# schematic.net
KiCad netlist of a schematic drawn in EAGLE
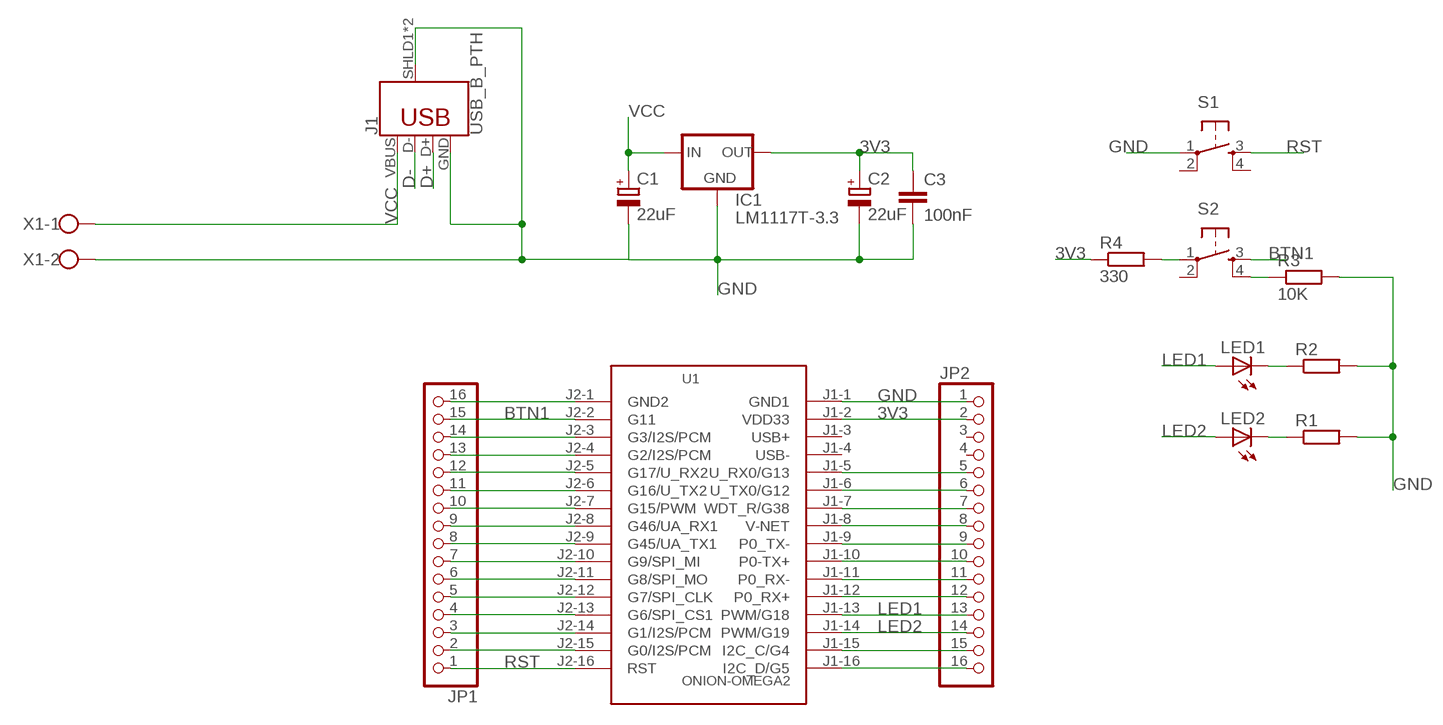
[diagram p0: schematic, sheet 1]

(export (version "E")
  (design (tool "Eeschema 10.0.6"))
  (components
    (comp (ref "C1")
      (value "22uF")
      (footprint "eagle-import:E2,5-5")
      (libsource (lib "eagle-import") (part "CPOL-EUE2.5-5"))
    )
    (comp (ref "C2")
      (value "22uF")
      (footprint "eagle-import:E2,5-5")
      (libsource (lib "eagle-import") (part "CPOL-EUE2.5-5"))
    )
    (comp (ref "C3")
      (value "100nF")
      (footprint "eagle-import:C050-025X075")
      (libsource (lib "eagle-import") (part "C-EU050-025X075"))
    )
    (comp (ref "IC1")
      (value "LM1117T-3.3")
      (footprint "eagle-import:TO220")
      (libsource (lib "eagle-import") (part "LM1117T-3.3"))
    )
    (comp (ref "J1")
      (value "USB_B_PTH")
      (footprint "eagle-import:USB-B-PTH")
      (libsource (lib "eagle-import") (part "USB_B_PTH"))
    )
    (comp (ref "JP1")
      (value "PINHD-1X16")
      (footprint "eagle-import:1X16")
      (libsource (lib "eagle-import") (part "PINHD-1X16"))
    )
    (comp (ref "JP2")
      (value "PINHD-1X16")
      (footprint "eagle-import:1X16")
      (libsource (lib "eagle-import") (part "PINHD-1X16"))
    )
    (comp (ref "LED1")
      (value "LED5MM")
      (footprint "eagle-import:LED5MM")
      (libsource (lib "eagle-import") (part "LED5MM"))
    )
    (comp (ref "LED2")
      (value "LED5MM")
      (footprint "eagle-import:LED5MM")
      (libsource (lib "eagle-import") (part "LED5MM"))
    )
    (comp (ref "R1")
      (value "R-EU_0204/7")
      (footprint "eagle-import:0204_7")
      (libsource (lib "eagle-import") (part "R-EU_0204/7"))
    )
    (comp (ref "R2")
      (value "R-EU_0204/7")
      (footprint "eagle-import:0204_7")
      (libsource (lib "eagle-import") (part "R-EU_0204/7"))
    )
    (comp (ref "R3")
      (value "10K")
      (footprint "eagle-import:0204_7")
      (libsource (lib "eagle-import") (part "R-EU_0204/7"))
    )
    (comp (ref "R4")
      (value "330")
      (footprint "eagle-import:0204_7")
      (libsource (lib "eagle-import") (part "R-EU_0204/7"))
    )
    (comp (ref "S1")
      (value "TAC_SWITCHPTH")
      (footprint "eagle-import:TACTILE-PTH")
      (libsource (lib "eagle-import") (part "TAC_SWITCHPTH"))
    )
    (comp (ref "S2")
      (value "TAC_SWITCHPTH")
      (footprint "eagle-import:TACTILE-PTH")
      (libsource (lib "eagle-import") (part "TAC_SWITCHPTH"))
    )
    (comp (ref "U1")
      (value "ONION-OMEGA2")
      (footprint "eagle-import:ONION-2MM-2X16")
      (libsource (lib "eagle-import") (part "ONION-OMEGA2"))
    )
    (comp (ref "X1")
      (value "W237-102")
      (footprint "eagle-import:W237-102")
      (fields (field (name "MPN") "237-102"))
      (libsource (lib "eagle-import") (part "W237-102"))
    )
  )
  (nets
    (net (code "1") (name "/3V3") (class "Default")
      (node (ref "C2") (pin "+") (pinfunction "+_+") (pintype "passive"))
      (node (ref "C3") (pin "1") (pinfunction "1_1") (pintype "passive"))
      (node (ref "IC1") (pin "2") (pinfunction "OUT_2") (pintype "passive"))
      (node (ref "JP2") (pin "2") (pinfunction "2_2") (pintype "passive"))
      (node (ref "R4") (pin "1") (pinfunction "1_1") (pintype "passive"))
      (node (ref "U1") (pin "J1-2") (pinfunction "VDD33_J1-2") (pintype "bidirectional"))
    )
    (net (code "2") (name "/BTN1") (class "Default")
      (node (ref "JP1") (pin "15") (pinfunction "15_15") (pintype "passive"))
      (node (ref "S2") (pin "3") (pinfunction "3_3") (pintype "passive"))
      (node (ref "U1") (pin "J2-2") (pinfunction "G11_J2-2") (pintype "bidirectional"))
    )
    (net (code "3") (name "/D+") (class "Default")
      (node (ref "J1") (pin "D+") (pinfunction "D+_D+") (pintype "bidirectional"))
    )
    (net (code "4") (name "/D-") (class "Default")
      (node (ref "J1") (pin "D-") (pinfunction "D-_D-") (pintype "bidirectional"))
    )
    (net (code "5") (name "/GND") (class "Default")
      (node (ref "C1") (pin "-") (pinfunction "-_-") (pintype "passive"))
      (node (ref "C2") (pin "-") (pinfunction "-_-") (pintype "passive"))
      (node (ref "C3") (pin "2") (pinfunction "2_2") (pintype "passive"))
      (node (ref "IC1") (pin "1") (pinfunction "GND_1") (pintype "input"))
      (node (ref "J1") (pin "GND") (pinfunction "GND_GND") (pintype "power_in"))
      (node (ref "J1") (pin "SHLD1") (pinfunction "SHIELD_SHLD1") (pintype "bidirectional"))
      (node (ref "J1") (pin "SHLD2") (pinfunction "SHIELD_SHLD2") (pintype "bidirectional"))
      (node (ref "JP2") (pin "1") (pinfunction "1_1") (pintype "passive"))
      (node (ref "R1") (pin "2") (pinfunction "2_2") (pintype "passive"))
      (node (ref "R2") (pin "2") (pinfunction "2_2") (pintype "passive"))
      (node (ref "R3") (pin "2") (pinfunction "2_2") (pintype "passive"))
      (node (ref "S1") (pin "1") (pinfunction "1_1") (pintype "passive"))
      (node (ref "U1") (pin "J1-1") (pinfunction "GND1_J1-1") (pintype "bidirectional"))
      (node (ref "X1") (pin "2") (pinfunction "KL_2") (pintype "passive"))
    )
    (net (code "6") (name "/LED1") (class "Default")
      (node (ref "JP2") (pin "13") (pinfunction "13_13") (pintype "passive"))
      (node (ref "LED1") (pin "A") (pinfunction "A_A") (pintype "passive"))
      (node (ref "U1") (pin "J1-13") (pinfunction "PWM/G18_J1-13") (pintype "bidirectional"))
    )
    (net (code "7") (name "/LED2") (class "Default")
      (node (ref "JP2") (pin "14") (pinfunction "14_14") (pintype "passive"))
      (node (ref "LED2") (pin "A") (pinfunction "A_A") (pintype "passive"))
      (node (ref "U1") (pin "J1-14") (pinfunction "PWM/G19_J1-14") (pintype "bidirectional"))
    )
    (net (code "8") (name "/RST") (class "Default")
      (node (ref "JP1") (pin "1") (pinfunction "1_1") (pintype "passive"))
      (node (ref "S1") (pin "3") (pinfunction "3_3") (pintype "passive"))
      (node (ref "U1") (pin "J2-16") (pinfunction "RST_J2-16") (pintype "bidirectional"))
    )
    (net (code "9") (name "/VCC") (class "Default")
      (node (ref "C1") (pin "+") (pinfunction "+_+") (pintype "passive"))
      (node (ref "IC1") (pin "3") (pinfunction "IN_3") (pintype "input"))
      (node (ref "J1") (pin "VBUS") (pinfunction "VBUS_VBUS") (pintype "power_in"))
      (node (ref "X1") (pin "1") (pinfunction "KL_1") (pintype "passive"))
    )
    (net (code "10") (name "Net-(LED1-C)") (class "Default")
      (node (ref "LED1") (pin "K") (pinfunction "C_K") (pintype "passive"))
      (node (ref "R2") (pin "1") (pinfunction "1_1") (pintype "passive"))
    )
    (net (code "11") (name "Net-(LED2-C)") (class "Default")
      (node (ref "LED2") (pin "K") (pinfunction "C_K") (pintype "passive"))
      (node (ref "R1") (pin "1") (pinfunction "1_1") (pintype "passive"))
    )
    (net (code "12") (name "Net-(R3-Pad1)") (class "Default")
      (node (ref "R3") (pin "1") (pinfunction "1_1") (pintype "passive"))
      (node (ref "S2") (pin "4") (pinfunction "4_4") (pintype "passive"))
    )
    (net (code "13") (name "Net-(R4-Pad2)") (class "Default")
      (node (ref "R4") (pin "2") (pinfunction "2_2") (pintype "passive"))
      (node (ref "S2") (pin "1") (pinfunction "1_1") (pintype "passive"))
    )
    (net (code "14") (name "Net-(U1-G0{slash}I2S{slash}PCM)") (class "Default")
      (node (ref "JP1") (pin "2") (pinfunction "2_2") (pintype "passive"))
      (node (ref "U1") (pin "J2-15") (pinfunction "G0/I2S/PCM_J2-15") (pintype "bidirectional"))
    )
    (net (code "15") (name "Net-(U1-G1{slash}I2S{slash}PCM)") (class "Default")
      (node (ref "JP1") (pin "3") (pinfunction "3_3") (pintype "passive"))
      (node (ref "U1") (pin "J2-14") (pinfunction "G1/I2S/PCM_J2-14") (pintype "bidirectional"))
    )
    (net (code "16") (name "Net-(U1-G2{slash}I2S{slash}PCM)") (class "Default")
      (node (ref "JP1") (pin "13") (pinfunction "13_13") (pintype "passive"))
      (node (ref "U1") (pin "J2-4") (pinfunction "G2/I2S/PCM_J2-4") (pintype "bidirectional"))
    )
    (net (code "17") (name "Net-(U1-G3{slash}I2S{slash}PCM)") (class "Default")
      (node (ref "JP1") (pin "14") (pinfunction "14_14") (pintype "passive"))
      (node (ref "U1") (pin "J2-3") (pinfunction "G3/I2S/PCM_J2-3") (pintype "bidirectional"))
    )
    (net (code "18") (name "Net-(U1-G6{slash}SPI_CS1)") (class "Default")
      (node (ref "JP1") (pin "4") (pinfunction "4_4") (pintype "passive"))
      (node (ref "U1") (pin "J2-13") (pinfunction "G6/SPI_CS1_J2-13") (pintype "bidirectional"))
    )
    (net (code "19") (name "Net-(U1-G7{slash}SPI_CLK)") (class "Default")
      (node (ref "JP1") (pin "5") (pinfunction "5_5") (pintype "passive"))
      (node (ref "U1") (pin "J2-12") (pinfunction "G7/SPI_CLK_J2-12") (pintype "bidirectional"))
    )
    (net (code "20") (name "Net-(U1-G8{slash}SPI_MO)") (class "Default")
      (node (ref "JP1") (pin "6") (pinfunction "6_6") (pintype "passive"))
      (node (ref "U1") (pin "J2-11") (pinfunction "G8/SPI_MO_J2-11") (pintype "bidirectional"))
    )
    (net (code "21") (name "Net-(U1-G9{slash}SPI_MI)") (class "Default")
      (node (ref "JP1") (pin "7") (pinfunction "7_7") (pintype "passive"))
      (node (ref "U1") (pin "J2-10") (pinfunction "G9/SPI_MI_J2-10") (pintype "bidirectional"))
    )
    (net (code "22") (name "Net-(U1-G15{slash}PWM)") (class "Default")
      (node (ref "JP1") (pin "10") (pinfunction "10_10") (pintype "passive"))
      (node (ref "U1") (pin "J2-7") (pinfunction "G15/PWM_J2-7") (pintype "bidirectional"))
    )
    (net (code "23") (name "Net-(U1-G16{slash}U_TX2)") (class "Default")
      (node (ref "JP1") (pin "11") (pinfunction "11_11") (pintype "passive"))
      (node (ref "U1") (pin "J2-6") (pinfunction "G16/U_TX2_J2-6") (pintype "bidirectional"))
    )
    (net (code "24") (name "Net-(U1-G17{slash}U_RX2)") (class "Default")
      (node (ref "JP1") (pin "12") (pinfunction "12_12") (pintype "passive"))
      (node (ref "U1") (pin "J2-5") (pinfunction "G17/U_RX2_J2-5") (pintype "bidirectional"))
    )
    (net (code "25") (name "Net-(U1-G45{slash}UA_TX1)") (class "Default")
      (node (ref "JP1") (pin "8") (pinfunction "8_8") (pintype "passive"))
      (node (ref "U1") (pin "J2-9") (pinfunction "G45/UA_TX1_J2-9") (pintype "bidirectional"))
    )
    (net (code "26") (name "Net-(U1-G46{slash}UA_RX1)") (class "Default")
      (node (ref "JP1") (pin "9") (pinfunction "9_9") (pintype "passive"))
      (node (ref "U1") (pin "J2-8") (pinfunction "G46/UA_RX1_J2-8") (pintype "bidirectional"))
    )
    (net (code "27") (name "Net-(U1-GND2)") (class "Default")
      (node (ref "JP1") (pin "16") (pinfunction "16_16") (pintype "passive"))
      (node (ref "U1") (pin "J2-1") (pinfunction "GND2_J2-1") (pintype "bidirectional"))
    )
    (net (code "28") (name "Net-(U1-I2C_C{slash}G4)") (class "Default")
      (node (ref "JP2") (pin "15") (pinfunction "15_15") (pintype "passive"))
      (node (ref "U1") (pin "J1-15") (pinfunction "I2C_C/G4_J1-15") (pintype "bidirectional"))
    )
    (net (code "29") (name "Net-(U1-I2C_D{slash}G5)") (class "Default")
      (node (ref "JP2") (pin "16") (pinfunction "16_16") (pintype "passive"))
      (node (ref "U1") (pin "J1-16") (pinfunction "I2C_D/G5_J1-16") (pintype "bidirectional"))
    )
    (net (code "30") (name "Net-(U1-P0-TX+)") (class "Default")
      (node (ref "JP2") (pin "10") (pinfunction "10_10") (pintype "passive"))
      (node (ref "U1") (pin "J1-10") (pinfunction "P0-TX+_J1-10") (pintype "bidirectional"))
    )
    (net (code "31") (name "Net-(U1-P0_RX+)") (class "Default")
      (node (ref "JP2") (pin "12") (pinfunction "12_12") (pintype "passive"))
      (node (ref "U1") (pin "J1-12") (pinfunction "P0_RX+_J1-12") (pintype "bidirectional"))
    )
    (net (code "32") (name "Net-(U1-P0_RX-)") (class "Default")
      (node (ref "JP2") (pin "11") (pinfunction "11_11") (pintype "passive"))
      (node (ref "U1") (pin "J1-11") (pinfunction "P0_RX-_J1-11") (pintype "bidirectional"))
    )
    (net (code "33") (name "Net-(U1-P0_TX-)") (class "Default")
      (node (ref "JP2") (pin "9") (pinfunction "9_9") (pintype "passive"))
      (node (ref "U1") (pin "J1-9") (pinfunction "P0_TX-_J1-9") (pintype "bidirectional"))
    )
    (net (code "34") (name "Net-(U1-U_RX0{slash}G13)") (class "Default")
      (node (ref "JP2") (pin "5") (pinfunction "5_5") (pintype "passive"))
      (node (ref "U1") (pin "J1-5") (pinfunction "U_RX0/G13_J1-5") (pintype "bidirectional"))
    )
    (net (code "35") (name "Net-(U1-U_TX0{slash}G12)") (class "Default")
      (node (ref "JP2") (pin "6") (pinfunction "6_6") (pintype "passive"))
      (node (ref "U1") (pin "J1-6") (pinfunction "U_TX0/G12_J1-6") (pintype "bidirectional"))
    )
    (net (code "36") (name "Net-(U1-V-NET)") (class "Default")
      (node (ref "JP2") (pin "8") (pinfunction "8_8") (pintype "passive"))
      (node (ref "U1") (pin "J1-8") (pinfunction "V-NET_J1-8") (pintype "bidirectional"))
    )
    (net (code "37") (name "Net-(U1-WDT_R{slash}G38)") (class "Default")
      (node (ref "JP2") (pin "7") (pinfunction "7_7") (pintype "passive"))
      (node (ref "U1") (pin "J1-7") (pinfunction "WDT_R/G38_J1-7") (pintype "bidirectional"))
    )
    (net (code "38") (name "unconnected-(JP2-Pad3)") (class "Default")
      (node (ref "JP2") (pin "3") (pinfunction "3_3") (pintype "passive"))
    )
    (net (code "39") (name "unconnected-(JP2-Pad4)") (class "Default")
      (node (ref "JP2") (pin "4") (pinfunction "4_4") (pintype "passive"))
    )
    (net (code "40") (name "unconnected-(S1-Pad2)") (class "Default")
      (node (ref "S1") (pin "2") (pinfunction "2_2") (pintype "passive"))
    )
    (net (code "41") (name "unconnected-(S1-Pad4)") (class "Default")
      (node (ref "S1") (pin "4") (pinfunction "4_4") (pintype "passive"))
    )
    (net (code "42") (name "unconnected-(S2-Pad2)") (class "Default")
      (node (ref "S2") (pin "2") (pinfunction "2_2") (pintype "passive"))
    )
    (net (code "43") (name "unconnected-(U1-USB+-PadJ1-3)") (class "Default")
      (node (ref "U1") (pin "J1-3") (pinfunction "USB+_J1-3") (pintype "bidirectional"))
    )
    (net (code "44") (name "unconnected-(U1-USB--PadJ1-4)") (class "Default")
      (node (ref "U1") (pin "J1-4") (pinfunction "USB-_J1-4") (pintype "bidirectional"))
    )
  )
)
